# postkasse.net
KiCad netlist of a schematic drawn in EAGLE
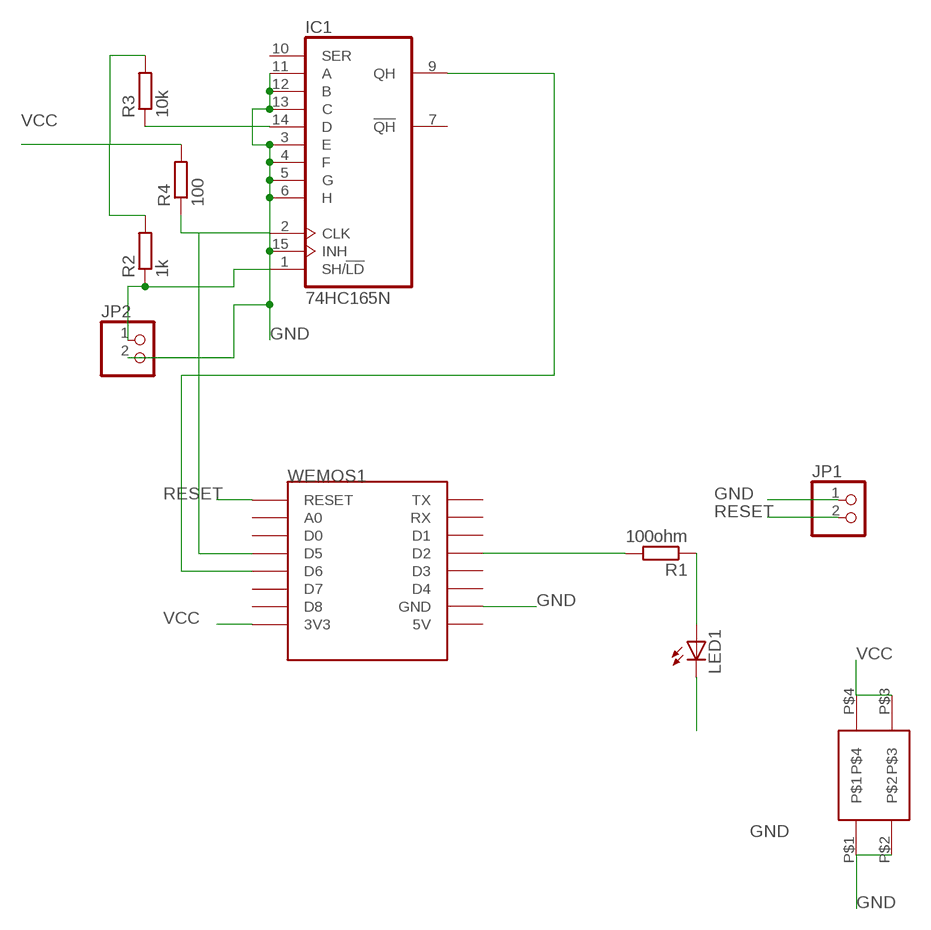
[diagram p0: schematic, sheet 1]

(export (version "E")
  (design (tool "Eeschema 10.0.6"))
  (components
    (comp (ref "IC1")
      (value "74HC165N")
      (footprint "eagle-import:DIL16")
      (libsource (lib "eagle-import") (part "74165NHC"))
    )
    (comp (ref "JP1")
      (value "PINHD-1X2")
      (footprint "eagle-import:1X02")
      (libsource (lib "eagle-import") (part "PINHD-1X2"))
    )
    (comp (ref "JP2")
      (value "PINHD-1X2")
      (footprint "eagle-import:1X02")
      (libsource (lib "eagle-import") (part "PINHD-1X2"))
    )
    (comp (ref "LED1")
      (value "LED5MM")
      (footprint "eagle-import:LED5MM")
      (libsource (lib "eagle-import") (part "LED5MM"))
    )
    (comp (ref "R1")
      (value "100ohm")
      (footprint "eagle-import:0204_7")
      (libsource (lib "eagle-import") (part "R-EU_0204/7"))
    )
    (comp (ref "R2")
      (value "1k")
      (footprint "eagle-import:0204_7")
      (libsource (lib "eagle-import") (part "R-EU_0204/7"))
    )
    (comp (ref "R3")
      (value "10k")
      (footprint "eagle-import:0204_7")
      (libsource (lib "eagle-import") (part "R-EU_0204/7"))
    )
    (comp (ref "R4")
      (value "100")
      (footprint "eagle-import:0204_7")
      (libsource (lib "eagle-import") (part "R-EU_0204/7"))
    )
    (comp (ref "U$1")
      (value "BAT18650")
      (footprint "eagle-import:BAT18650")
      (libsource (lib "eagle-import") (part "BAT18650"))
    )
    (comp (ref "WEMOS1")
      (value "WEMOS-D1-MINI")
      (footprint "eagle-import:WEMOS-D1-MINI")
      (libsource (lib "eagle-import") (part "WEMOS-D1-MINI"))
    )
  )
  (nets
    (net (code "1") (name "/GND") (class "Default")
      (node (ref "IC1") (pin "11") (pinfunction "A_11") (pintype "input"))
      (node (ref "IC1") (pin "12") (pinfunction "B_12") (pintype "input"))
      (node (ref "IC1") (pin "13") (pinfunction "C_13") (pintype "input"))
      (node (ref "IC1") (pin "15") (pinfunction "INH_15") (pintype "input"))
      (node (ref "IC1") (pin "3") (pinfunction "E_3") (pintype "input"))
      (node (ref "IC1") (pin "4") (pinfunction "F_4") (pintype "input"))
      (node (ref "IC1") (pin "5") (pinfunction "G_5") (pintype "input"))
      (node (ref "IC1") (pin "6") (pinfunction "H_6") (pintype "input"))
      (node (ref "JP1") (pin "1") (pinfunction "1_1") (pintype "passive"))
      (node (ref "JP2") (pin "2") (pinfunction "2_2") (pintype "passive"))
      (node (ref "LED1") (pin "K") (pinfunction "C_K") (pintype "passive"))
      (node (ref "U$1") (pin "P$1") (pinfunction "P$1_P$1") (pintype "bidirectional"))
      (node (ref "U$1") (pin "P$2") (pinfunction "P$2_P$2") (pintype "bidirectional"))
      (node (ref "WEMOS1") (pin "GND") (pinfunction "GND_GND") (pintype "bidirectional"))
    )
    (net (code "2") (name "/RESET") (class "Default")
      (node (ref "JP1") (pin "2") (pinfunction "2_2") (pintype "passive"))
      (node (ref "WEMOS1") (pin "RESET") (pinfunction "RESET_RESET") (pintype "bidirectional"))
    )
    (net (code "3") (name "/VCC") (class "Default")
      (node (ref "R2") (pin "2") (pinfunction "2_2") (pintype "passive"))
      (node (ref "R3") (pin "2") (pinfunction "2_2") (pintype "passive"))
      (node (ref "R4") (pin "2") (pinfunction "2_2") (pintype "passive"))
      (node (ref "U$1") (pin "P$3") (pinfunction "P$3_P$3") (pintype "bidirectional"))
      (node (ref "U$1") (pin "P$4") (pinfunction "P$4_P$4") (pintype "bidirectional"))
      (node (ref "WEMOS1") (pin "3V3") (pinfunction "3V3_3V3") (pintype "bidirectional"))
    )
    (net (code "4") (name "Net-(IC1A-CLK)") (class "Default")
      (node (ref "IC1") (pin "2") (pinfunction "CLK_2") (pintype "input"))
      (node (ref "R4") (pin "1") (pinfunction "1_1") (pintype "passive"))
      (node (ref "WEMOS1") (pin "D5") (pinfunction "D5_D5") (pintype "bidirectional"))
    )
    (net (code "5") (name "Net-(IC1A-D)") (class "Default")
      (node (ref "IC1") (pin "14") (pinfunction "D_14") (pintype "input"))
      (node (ref "R3") (pin "1") (pinfunction "1_1") (pintype "passive"))
    )
    (net (code "6") (name "Net-(IC1A-QH)") (class "Default")
      (node (ref "IC1") (pin "9") (pinfunction "QH_9") (pintype "output"))
      (node (ref "WEMOS1") (pin "D6") (pinfunction "D6_D6") (pintype "bidirectional"))
    )
    (net (code "7") (name "Net-(IC1A-SH{slash}~{LD})") (class "Default")
      (node (ref "IC1") (pin "1") (pinfunction "SH/~{LD}_1") (pintype "input"))
      (node (ref "JP2") (pin "1") (pinfunction "1_1") (pintype "passive"))
      (node (ref "R2") (pin "1") (pinfunction "1_1") (pintype "passive"))
    )
    (net (code "8") (name "Net-(LED1-PadA)") (class "Default")
      (node (ref "LED1") (pin "A") (pinfunction "A_A") (pintype "passive"))
      (node (ref "R1") (pin "1") (pinfunction "1_1") (pintype "passive"))
    )
    (net (code "9") (name "Net-(R1-Pad2)") (class "Default")
      (node (ref "R1") (pin "2") (pinfunction "2_2") (pintype "passive"))
      (node (ref "WEMOS1") (pin "D2") (pinfunction "D2_D2") (pintype "bidirectional"))
    )
    (net (code "10") (name "unconnected-(IC1A-SER-Pad10)") (class "Default")
      (node (ref "IC1") (pin "10") (pinfunction "SER_10") (pintype "input"))
    )
    (net (code "11") (name "unconnected-(IC1A-~{QH}-Pad7)") (class "Default")
      (node (ref "IC1") (pin "7") (pinfunction "~{QH}_7") (pintype "output"))
    )
    (net (code "12") (name "unconnected-(WEMOS1-Pad5V)") (class "Default")
      (node (ref "WEMOS1") (pin "5V") (pinfunction "5V_5V") (pintype "bidirectional"))
    )
    (net (code "13") (name "unconnected-(WEMOS1-PadA0)") (class "Default")
      (node (ref "WEMOS1") (pin "A0") (pinfunction "A0_A0") (pintype "bidirectional"))
    )
    (net (code "14") (name "unconnected-(WEMOS1-PadD0)") (class "Default")
      (node (ref "WEMOS1") (pin "D0") (pinfunction "D0_D0") (pintype "bidirectional"))
    )
    (net (code "15") (name "unconnected-(WEMOS1-PadD1)") (class "Default")
      (node (ref "WEMOS1") (pin "D1") (pinfunction "D1_D1") (pintype "bidirectional"))
    )
    (net (code "16") (name "unconnected-(WEMOS1-PadD3)") (class "Default")
      (node (ref "WEMOS1") (pin "D3") (pinfunction "D3_D3") (pintype "bidirectional"))
    )
    (net (code "17") (name "unconnected-(WEMOS1-PadD4)") (class "Default")
      (node (ref "WEMOS1") (pin "D4") (pinfunction "D4_D4") (pintype "bidirectional"))
    )
    (net (code "18") (name "unconnected-(WEMOS1-PadD7)") (class "Default")
      (node (ref "WEMOS1") (pin "D7") (pinfunction "D7_D7") (pintype "bidirectional"))
    )
    (net (code "19") (name "unconnected-(WEMOS1-PadD8)") (class "Default")
      (node (ref "WEMOS1") (pin "D8") (pinfunction "D8_D8") (pintype "bidirectional"))
    )
    (net (code "20") (name "unconnected-(WEMOS1-PadRX)") (class "Default")
      (node (ref "WEMOS1") (pin "RX") (pinfunction "RX_RX") (pintype "bidirectional"))
    )
    (net (code "21") (name "unconnected-(WEMOS1-PadTX)") (class "Default")
      (node (ref "WEMOS1") (pin "TX") (pinfunction "TX_TX") (pintype "bidirectional"))
    )
  )
)
